# IndicatorBox.net
KiCad netlist of a schematic drawn in Altium Designer
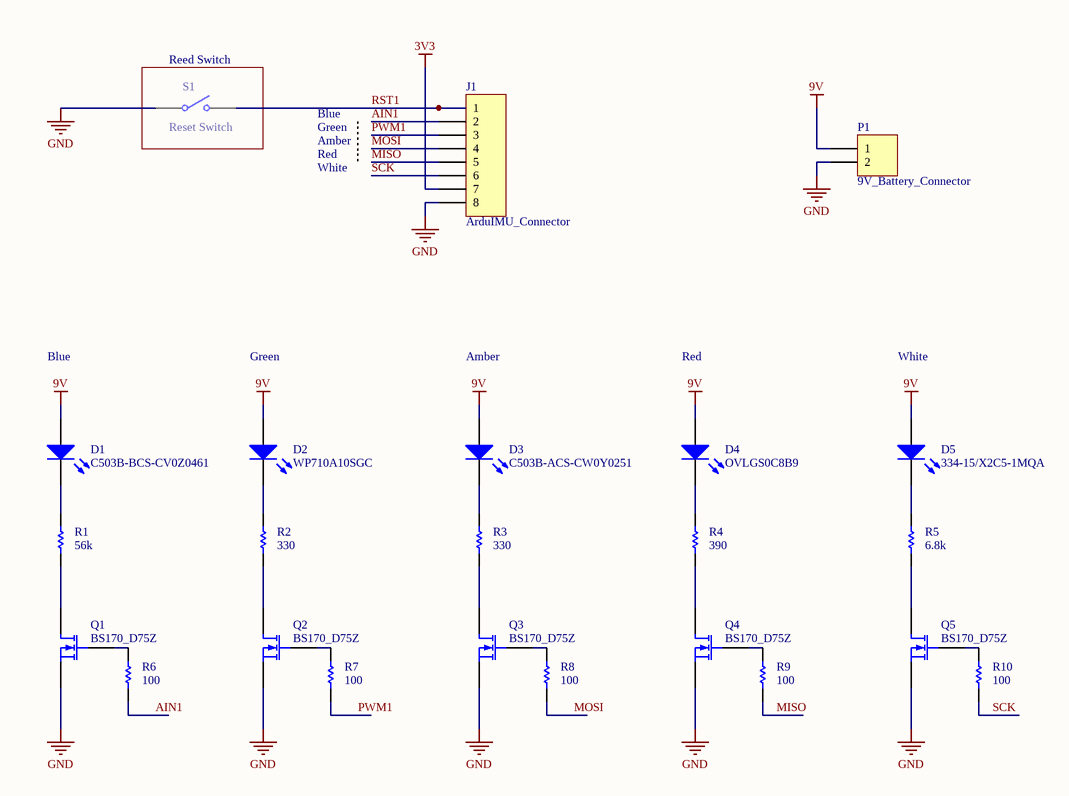
[diagram p0: IndicatorBox.SchDoc]

(export (version "E")
  (design (tool "Eeschema 10.0.6"))
  (components
    (comp (ref "D1")
      (value "C503B-BCS-CV0Z0461")
      (footprint "LED-0")
      (description "Typical INFRARED GaAs LED")
      (fields (field (name "PUBLISHER") "Altium Limited"))
      (libsource (lib "Miscellaneous Devices") (part "LED0"))
    )
    (comp (ref "D2")
      (value "WP710A10SGC")
      (footprint "LED-0")
      (description "Typical INFRARED GaAs LED")
      (fields (field (name "PUBLISHER") "Altium Limited"))
      (libsource (lib "Miscellaneous Devices") (part "LED0"))
    )
    (comp (ref "D3")
      (value "C503B-ACS-CW0Y0251")
      (footprint "LED-0")
      (description "Typical INFRARED GaAs LED")
      (fields (field (name "PUBLISHER") "Altium Limited"))
      (libsource (lib "Miscellaneous Devices") (part "LED0"))
    )
    (comp (ref "D4")
      (value "OVLGS0C8B9")
      (footprint "LED-0")
      (description "Typical INFRARED GaAs LED")
      (fields (field (name "PUBLISHER") "Altium Limited"))
      (libsource (lib "Miscellaneous Devices") (part "LED0"))
    )
    (comp (ref "D5")
      (value "334-15/X2C5-1MQA")
      (footprint "LED-0")
      (description "Typical INFRARED GaAs LED")
      (fields (field (name "PUBLISHER") "Altium Limited"))
      (libsource (lib "Miscellaneous Devices") (part "LED0"))
    )
    (comp (ref "J1")
      (value "ArduIMU_Connector")
      (footprint "HDR1X8")
      (description "Header, 8-Pin")
      (fields (field (name "PUBLISHER") "Altium Limited"))
      (libsource (lib "Miscellaneous Connectors") (part "Header 8"))
    )
    (comp (ref "P1")
      (value "9V_Battery_Connector")
      (footprint "HDR1X2")
      (description "Header, 2-Pin")
      (fields (field (name "PUBLISHER") "Altium Limited"))
      (libsource (lib "Miscellaneous Connectors") (part "Header 2"))
    )
    (comp (ref "Q1")
      (value "BS170_D75Z")
      (footprint "E3")
      (description "N-Channel MOSFET")
      (fields (field (name "PUBLISHER") "Altium Limited"))
      (libsource (lib "Miscellaneous Devices") (part "MOSFET-N"))
    )
    (comp (ref "Q2")
      (value "BS170_D75Z")
      (footprint "E3")
      (description "N-Channel MOSFET")
      (fields (field (name "PUBLISHER") "Altium Limited"))
      (libsource (lib "Miscellaneous Devices") (part "MOSFET-N"))
    )
    (comp (ref "Q3")
      (value "BS170_D75Z")
      (footprint "E3")
      (description "N-Channel MOSFET")
      (fields (field (name "PUBLISHER") "Altium Limited"))
      (libsource (lib "Miscellaneous Devices") (part "MOSFET-N"))
    )
    (comp (ref "Q4")
      (value "BS170_D75Z")
      (footprint "E3")
      (description "N-Channel MOSFET")
      (fields (field (name "PUBLISHER") "Altium Limited"))
      (libsource (lib "Miscellaneous Devices") (part "MOSFET-N"))
    )
    (comp (ref "Q5")
      (value "BS170_D75Z")
      (footprint "E3")
      (description "N-Channel MOSFET")
      (fields (field (name "PUBLISHER") "Altium Limited"))
      (libsource (lib "Miscellaneous Devices") (part "MOSFET-N"))
    )
    (comp (ref "R1")
      (value "56k")
      (footprint "AXIAL-0.3")
      (description "Resistor")
      (fields (field (name "PUBLISHER") "Altium Limited"))
      (libsource (lib "Miscellaneous Devices") (part "Res1"))
    )
    (comp (ref "R2")
      (value "330")
      (footprint "AXIAL-0.3")
      (description "Resistor")
      (fields (field (name "PUBLISHER") "Altium Limited"))
      (libsource (lib "Miscellaneous Devices") (part "Res1"))
    )
    (comp (ref "R3")
      (value "330")
      (footprint "AXIAL-0.3")
      (description "Resistor")
      (fields (field (name "PUBLISHER") "Altium Limited"))
      (libsource (lib "Miscellaneous Devices") (part "Res1"))
    )
    (comp (ref "R4")
      (value "390")
      (footprint "AXIAL-0.3")
      (description "Resistor")
      (fields (field (name "PUBLISHER") "Altium Limited"))
      (libsource (lib "Miscellaneous Devices") (part "Res1"))
    )
    (comp (ref "R5")
      (value "6.8k")
      (footprint "AXIAL-0.3")
      (description "Resistor")
      (fields (field (name "PUBLISHER") "Altium Limited"))
      (libsource (lib "Miscellaneous Devices") (part "Res1"))
    )
    (comp (ref "R6")
      (value "100")
      (footprint "AXIAL-0.3")
      (description "Resistor")
      (fields (field (name "PUBLISHER") "Altium Limited"))
      (libsource (lib "Miscellaneous Devices") (part "Res1"))
    )
    (comp (ref "R7")
      (value "100")
      (footprint "AXIAL-0.3")
      (description "Resistor")
      (fields (field (name "PUBLISHER") "Altium Limited"))
      (libsource (lib "Miscellaneous Devices") (part "Res1"))
    )
    (comp (ref "R8")
      (value "100")
      (footprint "AXIAL-0.3")
      (description "Resistor")
      (fields (field (name "PUBLISHER") "Altium Limited"))
      (libsource (lib "Miscellaneous Devices") (part "Res1"))
    )
    (comp (ref "R9")
      (value "100")
      (footprint "AXIAL-0.3")
      (description "Resistor")
      (fields (field (name "PUBLISHER") "Altium Limited"))
      (libsource (lib "Miscellaneous Devices") (part "Res1"))
    )
    (comp (ref "R10")
      (value "100")
      (footprint "AXIAL-0.3")
      (description "Resistor")
      (fields (field (name "PUBLISHER") "Altium Limited"))
      (libsource (lib "Miscellaneous Devices") (part "Res1"))
    )
    (comp (ref "S1")
      (value "Reset Switch")
      (footprint "SPST-2")
      (description "Single-Pole, Single-Throw Switch")
      (fields (field (name "PUBLISHER") "Altium Limited"))
      (libsource (lib "Miscellaneous Devices") (part "SW-SPST"))
    )
  )
  (nets
    (net (code "1") (name "/AIN1") (class "Default")
      (node (ref "J1") (pin "2") (pinfunction "2_2") (pintype "passive"))
      (node (ref "R6") (pin "1") (pinfunction "1_1") (pintype "passive"))
    )
    (net (code "2") (name "/MISO") (class "Default")
      (node (ref "J1") (pin "5") (pinfunction "5_5") (pintype "passive"))
      (node (ref "R9") (pin "1") (pinfunction "1_1") (pintype "passive"))
    )
    (net (code "3") (name "/MOSI") (class "Default")
      (node (ref "J1") (pin "4") (pinfunction "4_4") (pintype "passive"))
      (node (ref "R8") (pin "1") (pinfunction "1_1") (pintype "passive"))
    )
    (net (code "4") (name "/PWM1") (class "Default")
      (node (ref "J1") (pin "3") (pinfunction "3_3") (pintype "passive"))
      (node (ref "R7") (pin "1") (pinfunction "1_1") (pintype "passive"))
    )
    (net (code "5") (name "/RST1") (class "Default")
      (node (ref "J1") (pin "1") (pinfunction "1_1") (pintype "passive"))
      (node (ref "S1") (pin "2") (pinfunction "NO_2") (pintype "passive"))
    )
    (net (code "6") (name "/SCK") (class "Default")
      (node (ref "J1") (pin "6") (pinfunction "6_6") (pintype "passive"))
      (node (ref "R10") (pin "1") (pinfunction "1_1") (pintype "passive"))
    )
    (net (code "7") (name "3V3") (class "Default")
      (node (ref "J1") (pin "7") (pinfunction "7_7") (pintype "passive"))
    )
    (net (code "8") (name "9V") (class "Default")
      (node (ref "D1") (pin "1") (pinfunction "A_1") (pintype "passive"))
      (node (ref "D2") (pin "1") (pinfunction "A_1") (pintype "passive"))
      (node (ref "D3") (pin "1") (pinfunction "A_1") (pintype "passive"))
      (node (ref "D4") (pin "1") (pinfunction "A_1") (pintype "passive"))
      (node (ref "D5") (pin "1") (pinfunction "A_1") (pintype "passive"))
      (node (ref "P1") (pin "1") (pinfunction "1_1") (pintype "passive"))
    )
    (net (code "9") (name "GND") (class "Default")
      (node (ref "J1") (pin "8") (pinfunction "8_8") (pintype "passive"))
      (node (ref "P1") (pin "2") (pinfunction "2_2") (pintype "passive"))
      (node (ref "Q1") (pin "3") (pinfunction "S_3") (pintype "passive"))
      (node (ref "Q2") (pin "3") (pinfunction "S_3") (pintype "passive"))
      (node (ref "Q3") (pin "3") (pinfunction "S_3") (pintype "passive"))
      (node (ref "Q4") (pin "3") (pinfunction "S_3") (pintype "passive"))
      (node (ref "Q5") (pin "3") (pinfunction "S_3") (pintype "passive"))
      (node (ref "S1") (pin "1") (pinfunction "COMMON_1") (pintype "passive"))
    )
    (net (code "10") (name "Net-(D1-K)") (class "Default")
      (node (ref "D1") (pin "2") (pinfunction "K_2") (pintype "passive"))
      (node (ref "R1") (pin "2") (pinfunction "2_2") (pintype "passive"))
    )
    (net (code "11") (name "Net-(D2-K)") (class "Default")
      (node (ref "D2") (pin "2") (pinfunction "K_2") (pintype "passive"))
      (node (ref "R2") (pin "2") (pinfunction "2_2") (pintype "passive"))
    )
    (net (code "12") (name "Net-(D3-K)") (class "Default")
      (node (ref "D3") (pin "2") (pinfunction "K_2") (pintype "passive"))
      (node (ref "R3") (pin "2") (pinfunction "2_2") (pintype "passive"))
    )
    (net (code "13") (name "Net-(D4-K)") (class "Default")
      (node (ref "D4") (pin "2") (pinfunction "K_2") (pintype "passive"))
      (node (ref "R4") (pin "2") (pinfunction "2_2") (pintype "passive"))
    )
    (net (code "14") (name "Net-(D5-K)") (class "Default")
      (node (ref "D5") (pin "2") (pinfunction "K_2") (pintype "passive"))
      (node (ref "R5") (pin "2") (pinfunction "2_2") (pintype "passive"))
    )
    (net (code "15") (name "Net-(Q1-D)") (class "Default")
      (node (ref "Q1") (pin "1") (pinfunction "D_1") (pintype "passive"))
      (node (ref "R1") (pin "1") (pinfunction "1_1") (pintype "passive"))
    )
    (net (code "16") (name "Net-(Q1-G)") (class "Default")
      (node (ref "Q1") (pin "2") (pinfunction "G_2") (pintype "passive"))
      (node (ref "R6") (pin "2") (pinfunction "2_2") (pintype "passive"))
    )
    (net (code "17") (name "Net-(Q2-D)") (class "Default")
      (node (ref "Q2") (pin "1") (pinfunction "D_1") (pintype "passive"))
      (node (ref "R2") (pin "1") (pinfunction "1_1") (pintype "passive"))
    )
    (net (code "18") (name "Net-(Q2-G)") (class "Default")
      (node (ref "Q2") (pin "2") (pinfunction "G_2") (pintype "passive"))
      (node (ref "R7") (pin "2") (pinfunction "2_2") (pintype "passive"))
    )
    (net (code "19") (name "Net-(Q3-D)") (class "Default")
      (node (ref "Q3") (pin "1") (pinfunction "D_1") (pintype "passive"))
      (node (ref "R3") (pin "1") (pinfunction "1_1") (pintype "passive"))
    )
    (net (code "20") (name "Net-(Q3-G)") (class "Default")
      (node (ref "Q3") (pin "2") (pinfunction "G_2") (pintype "passive"))
      (node (ref "R8") (pin "2") (pinfunction "2_2") (pintype "passive"))
    )
    (net (code "21") (name "Net-(Q4-D)") (class "Default")
      (node (ref "Q4") (pin "1") (pinfunction "D_1") (pintype "passive"))
      (node (ref "R4") (pin "1") (pinfunction "1_1") (pintype "passive"))
    )
    (net (code "22") (name "Net-(Q4-G)") (class "Default")
      (node (ref "Q4") (pin "2") (pinfunction "G_2") (pintype "passive"))
      (node (ref "R9") (pin "2") (pinfunction "2_2") (pintype "passive"))
    )
    (net (code "23") (name "Net-(Q5-D)") (class "Default")
      (node (ref "Q5") (pin "1") (pinfunction "D_1") (pintype "passive"))
      (node (ref "R5") (pin "1") (pinfunction "1_1") (pintype "passive"))
    )
    (net (code "24") (name "Net-(Q5-G)") (class "Default")
      (node (ref "Q5") (pin "2") (pinfunction "G_2") (pintype "passive"))
      (node (ref "R10") (pin "2") (pinfunction "2_2") (pintype "passive"))
    )
  )
)
